# isoSP_UART_Test_Board_rev1.net
KiCad netlist of a schematic drawn in EAGLE
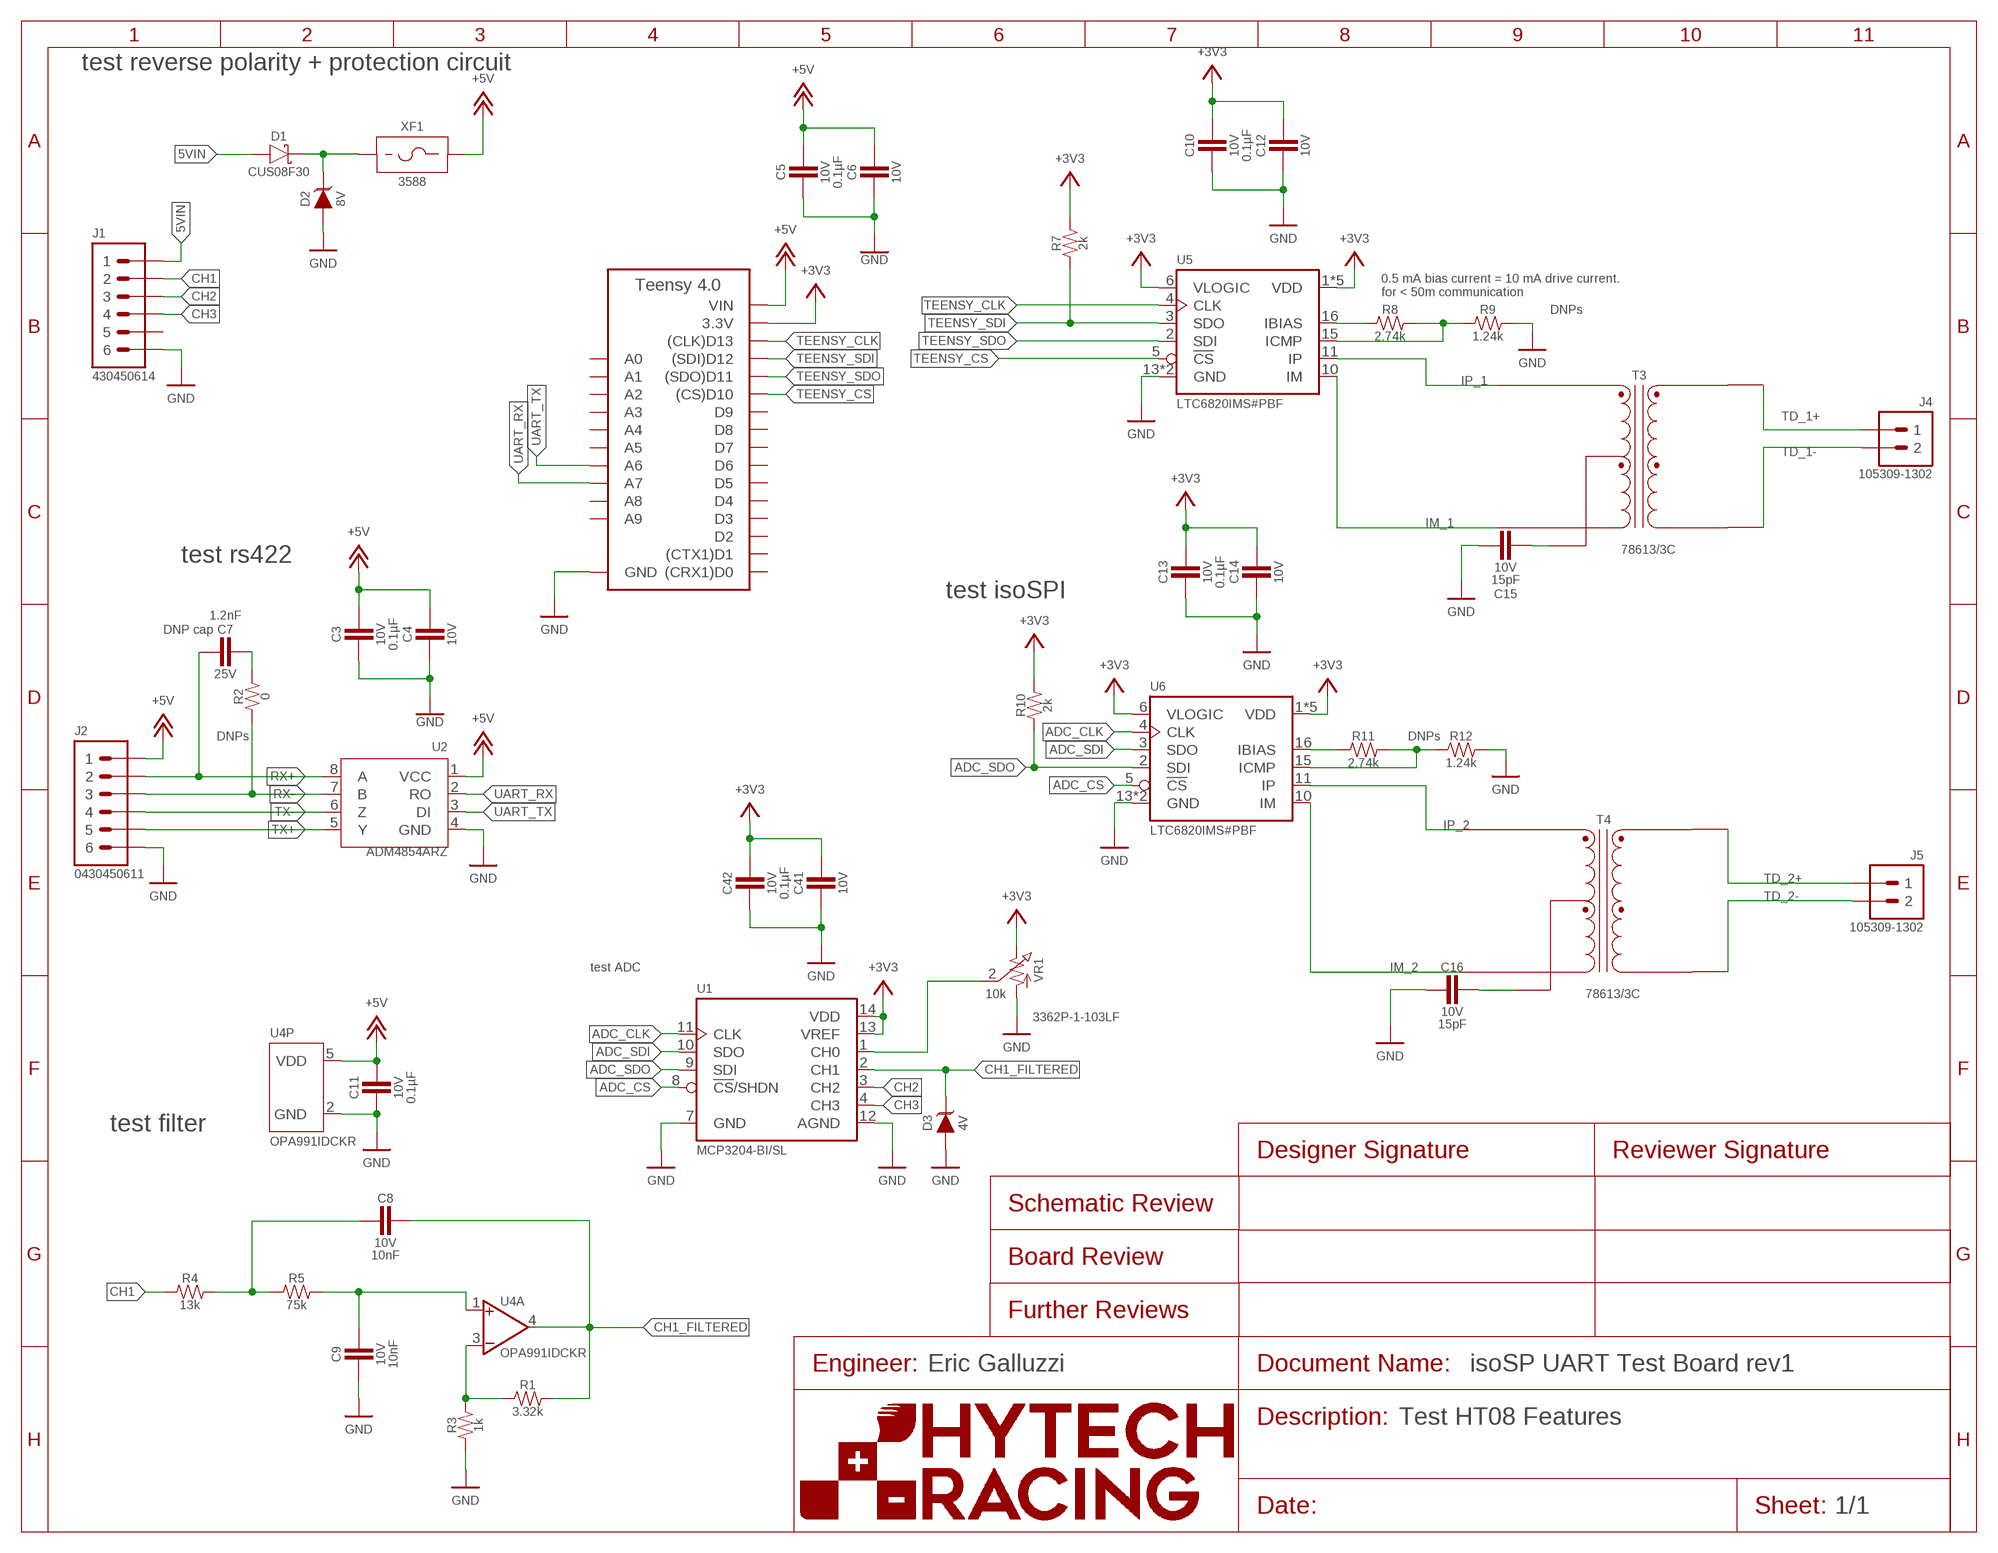
[diagram p0: schematic, sheet 1]

(export (version "E")
  (design (tool "Eeschema 10.0.6"))
  (components
    (comp (ref "A1")
      (value "TEENSY_4.0TH")
      (footprint "eagle-import:TEENSY_SHORT")
      (libsource (lib "eagle-import") (part "TEENSY_4.0TH"))
    )
    (comp (ref "C3")
      (value "CAPACITOR_0603_10V_0.1UF")
      (footprint "eagle-import:0603-CAP")
      (fields
        (field (name "CAPACITANCE") "0.1µF")
        (field (name "MANUFACTURER") "Vishay Vitramon")
        (field (name "MPN") "VJ0603Y104JXQPW1BC")
        (field (name "TOLERANCE") "5%")
        (field (name "VOLTAGE") "10V")
      )
      (libsource (lib "eagle-import") (part "CAPACITOR_?_060310V_0.1UF"))
    )
    (comp (ref "C4")
      (value "CAPACITOR_0603_10V_1UF")
      (footprint "eagle-import:0603-CAP")
      (fields
        (field (name "MANUFACTURER") "Yageo")
        (field (name "MPN") "CC0603KRX7R6BB105")
        (field (name "TOLERANCE") "10%")
        (field (name "VOLTAGE") "10V")
      )
      (libsource (lib "eagle-import") (part "CAPACITOR_?_060310V_1UF"))
    )
    (comp (ref "C5")
      (value "CAPACITOR_0603_10V_0.1UF")
      (footprint "eagle-import:0603-CAP")
      (fields
        (field (name "CAPACITANCE") "0.1µF")
        (field (name "MANUFACTURER") "Vishay Vitramon")
        (field (name "MPN") "VJ0603Y104JXQPW1BC")
        (field (name "TOLERANCE") "5%")
        (field (name "VOLTAGE") "10V")
      )
      (libsource (lib "eagle-import") (part "CAPACITOR_?_060310V_0.1UF"))
    )
    (comp (ref "C6")
      (value "CAPACITOR_0603_10V_1UF")
      (footprint "eagle-import:0603-CAP")
      (fields
        (field (name "MANUFACTURER") "Yageo")
        (field (name "MPN") "CC0603KRX7R6BB105")
        (field (name "TOLERANCE") "10%")
        (field (name "VOLTAGE") "10V")
      )
      (libsource (lib "eagle-import") (part "CAPACITOR_?_060310V_1UF"))
    )
    (comp (ref "C7")
      (value "CAPACITOR_0603_25V_1.2NF")
      (footprint "eagle-import:0603-CAP")
      (fields
        (field (name "CAPACITANCE") "1.2nF")
        (field (name "MANUFACTURER") "YAGEO")
        (field (name "MPN") "CC0603KRX7R8BB122")
        (field (name "TOLERANCE") "10%")
        (field (name "VOLTAGE") "25V")
      )
      (libsource (lib "eagle-import") (part "CAPACITOR_?_060325V_1.2NF"))
    )
    (comp (ref "C8")
      (value "CAPACITOR_0603_10V_10NF")
      (footprint "eagle-import:0603-CAP")
      (fields
        (field (name "CAPACITANCE") "10nF")
        (field (name "MANUFACTURER") "Yageo")
        (field (name "MPN") "CC0603KRX7R6BB103")
        (field (name "TOLERANCE") "10%")
        (field (name "VOLTAGE") "10V")
      )
      (libsource (lib "eagle-import") (part "CAPACITOR_?_060310V_10NF"))
    )
    (comp (ref "C9")
      (value "CAPACITOR_0603_10V_10NF")
      (footprint "eagle-import:0603-CAP")
      (fields
        (field (name "CAPACITANCE") "10nF")
        (field (name "MANUFACTURER") "Yageo")
        (field (name "MPN") "CC0603KRX7R6BB103")
        (field (name "TOLERANCE") "10%")
        (field (name "VOLTAGE") "10V")
      )
      (libsource (lib "eagle-import") (part "CAPACITOR_?_060310V_10NF"))
    )
    (comp (ref "C10")
      (value "CAPACITOR_0603_10V_0.1UF")
      (footprint "eagle-import:0603-CAP")
      (fields
        (field (name "CAPACITANCE") "0.1µF")
        (field (name "MANUFACTURER") "Vishay Vitramon")
        (field (name "MPN") "VJ0603Y104JXQPW1BC")
        (field (name "TOLERANCE") "5%")
        (field (name "VOLTAGE") "10V")
      )
      (libsource (lib "eagle-import") (part "CAPACITOR_?_060310V_0.1UF"))
    )
    (comp (ref "C11")
      (value "CAPACITOR_0603_10V_0.1UF")
      (footprint "eagle-import:0603-CAP")
      (fields
        (field (name "CAPACITANCE") "0.1µF")
        (field (name "MANUFACTURER") "Vishay Vitramon")
        (field (name "MPN") "VJ0603Y104JXQPW1BC")
        (field (name "TOLERANCE") "5%")
        (field (name "VOLTAGE") "10V")
      )
      (libsource (lib "eagle-import") (part "CAPACITOR_?_060310V_0.1UF"))
    )
    (comp (ref "C12")
      (value "CAPACITOR_0603_10V_1UF")
      (footprint "eagle-import:0603-CAP")
      (fields
        (field (name "MANUFACTURER") "Yageo")
        (field (name "MPN") "CC0603KRX7R6BB105")
        (field (name "TOLERANCE") "10%")
        (field (name "VOLTAGE") "10V")
      )
      (libsource (lib "eagle-import") (part "CAPACITOR_?_060310V_1UF"))
    )
    (comp (ref "C13")
      (value "CAPACITOR_0603_10V_0.1UF")
      (footprint "eagle-import:0603-CAP")
      (fields
        (field (name "CAPACITANCE") "0.1µF")
        (field (name "MANUFACTURER") "Vishay Vitramon")
        (field (name "MPN") "VJ0603Y104JXQPW1BC")
        (field (name "TOLERANCE") "5%")
        (field (name "VOLTAGE") "10V")
      )
      (libsource (lib "eagle-import") (part "CAPACITOR_?_060310V_0.1UF"))
    )
    (comp (ref "C14")
      (value "CAPACITOR_0603_10V_1UF")
      (footprint "eagle-import:0603-CAP")
      (fields
        (field (name "MANUFACTURER") "Yageo")
        (field (name "MPN") "CC0603KRX7R6BB105")
        (field (name "TOLERANCE") "10%")
        (field (name "VOLTAGE") "10V")
      )
      (libsource (lib "eagle-import") (part "CAPACITOR_?_060310V_1UF"))
    )
    (comp (ref "C15")
      (value "CAPACITOR_0603_10V_15PF")
      (footprint "eagle-import:0603-CAP")
      (fields
        (field (name "CAPACITANCE") "15pF")
        (field (name "MANUFACTURER") "Vishay Vitramon")
        (field (name "MPN") "VJ0603A150FXQPW1BC")
        (field (name "TOLERANCE") "1%")
        (field (name "VOLTAGE") "10V")
      )
      (libsource (lib "eagle-import") (part "CAPACITOR_?_060310V_15PF"))
    )
    (comp (ref "C16")
      (value "CAPACITOR_0603_10V_15PF")
      (footprint "eagle-import:0603-CAP")
      (fields
        (field (name "CAPACITANCE") "15pF")
        (field (name "MANUFACTURER") "Vishay Vitramon")
        (field (name "MPN") "VJ0603A150FXQPW1BC")
        (field (name "TOLERANCE") "1%")
        (field (name "VOLTAGE") "10V")
      )
      (libsource (lib "eagle-import") (part "CAPACITOR_?_060310V_15PF"))
    )
    (comp (ref "C41")
      (value "CAPACITOR_0603_10V_1UF")
      (footprint "eagle-import:0603-CAP")
      (fields
        (field (name "MANUFACTURER") "Yageo")
        (field (name "MPN") "CC0603KRX7R6BB105")
        (field (name "TOLERANCE") "10%")
        (field (name "VOLTAGE") "10V")
      )
      (libsource (lib "eagle-import") (part "CAPACITOR_?_060310V_1UF"))
    )
    (comp (ref "C42")
      (value "CAPACITOR_0603_10V_0.1UF")
      (footprint "eagle-import:0603-CAP")
      (fields
        (field (name "CAPACITANCE") "0.1µF")
        (field (name "MANUFACTURER") "Vishay Vitramon")
        (field (name "MPN") "VJ0603Y104JXQPW1BC")
        (field (name "TOLERANCE") "5%")
        (field (name "VOLTAGE") "10V")
      )
      (libsource (lib "eagle-import") (part "CAPACITOR_?_060310V_0.1UF"))
    )
    (comp (ref "D1")
      (value "SCHOTTKY_SOD323_30V")
      (footprint "eagle-import:SOD-323")
      (fields
        (field (name "MANUFACTURER") "Toshiba Semiconductor and Storage")
        (field (name "MPN") "CUS08F30")
        (field (name "VOLTAGE") "30V")
      )
      (libsource (lib "eagle-import") (part "SCHOTTKY_?_SOD32330V"))
    )
    (comp (ref "D2")
      (value "TVS__8V")
      (footprint "eagle-import:SOT-23")
      (fields
        (field (name "MANUFACTURER") "Vishay General Semiconductor - Diodes Division")
        (field (name "MPN") "GSOT08-E3-08")
        (field (name "VOLTAGE") "8V")
      )
      (libsource (lib "eagle-import") (part "TVS_?_8V"))
    )
    (comp (ref "D3")
      (value "TVS__4V")
      (footprint "eagle-import:SOT-23")
      (fields
        (field (name "MANUFACTURER") "Vishay General Semiconductor - Diodes Division")
        (field (name "MPN") "GSOT04-E3-08")
        (field (name "VOLTAGE") "4V")
      )
      (libsource (lib "eagle-import") (part "TVS_?_4V"))
    )
    (comp (ref "J1")
      (value "CONNECTOR-6_μF_T_V_BLACK")
      (footprint "eagle-import:MOLEX_MICROFIT_PTH_VERTICAL_06_DUAL")
      (fields (field (name "MANUFACTURER") "Molex") (field (name "MPN") "430450614"))
      (libsource (lib "eagle-import") (part "CONNECTOR-6_?_μF_T_VBLACK"))
    )
    (comp (ref "J2")
      (value "CONNECTOR-6_μF_S_RA_")
      (footprint "eagle-import:MOLEX_MICROFIT_SMD_RIGHTANGLE_06_DUAL")
      (fields (field (name "MPN") "0430450611") (field (name "MANUFACTURER") "Molex"))
      (libsource (lib "eagle-import") (part "CONNECTOR-6_?_μF_S_RA"))
    )
    (comp (ref "J4")
      (value "CONNECTOR-2_MOLEX_NANOFIT_PTH_VERTICAL_02_BLACK")
      (footprint "eagle-import:MOLEX_NANOFIT_PTH_02")
      (fields (field (name "MANUFACTURER") "Molex") (field (name "MPN") "105309-1302"))
      (libsource (lib "eagle-import") (part "CONNECTOR-2_?_MOLEX_NANOFIT_PTH_VERTICAL_02BLACK"))
    )
    (comp (ref "J5")
      (value "CONNECTOR-2_MOLEX_NANOFIT_PTH_VERTICAL_02_BLACK")
      (footprint "eagle-import:MOLEX_NANOFIT_PTH_02")
      (fields (field (name "MANUFACTURER") "Molex") (field (name "MPN") "105309-1302"))
      (libsource (lib "eagle-import") (part "CONNECTOR-2_?_MOLEX_NANOFIT_PTH_VERTICAL_02BLACK"))
    )
    (comp (ref "R1")
      (value "RESISTOR_0603_3.32K")
      (footprint "eagle-import:0603-RES")
      (fields
        (field (name "MANUFACTURER") "Yageo")
        (field (name "MPN") "RT0603BRD073K32L")
        (field (name "POWER") "0.1W")
        (field (name "RESISTANCE") "3.32k")
      )
      (libsource (lib "eagle-import") (part "RESISTOR_?_06033.32K"))
    )
    (comp (ref "R2")
      (value "RESISTOR_0603_0")
      (footprint "eagle-import:0603-RES")
      (fields
        (field (name "MANUFACTURER") "Yageo")
        (field (name "MPN") "RC0603FR-070RL")
        (field (name "POWER") "0.1W")
        (field (name "RESISTANCE") "0")
      )
      (libsource (lib "eagle-import") (part "RESISTOR_?_06030"))
    )
    (comp (ref "R3")
      (value "RESISTOR_0603_1K")
      (footprint "eagle-import:0603-RES")
      (fields
        (field (name "MANUFACTURER") "TE Connectivity Passive Product")
        (field (name "MPN") " CPF-A-0603B1K0E")
        (field (name "POWER") "0.0625W")
        (field (name "RESISTANCE") "1k")
      )
      (libsource (lib "eagle-import") (part "RESISTOR_?_06031K"))
    )
    (comp (ref "R4")
      (value "RESISTOR_0603_13K")
      (footprint "eagle-import:0603-RES")
      (fields
        (field (name "MANUFACTURER") "Panasonic Electronic Components")
        (field (name "MPN") "ERA-3ARW133V")
        (field (name "POWER") "0.1W")
        (field (name "RESISTANCE") "13k")
      )
      (libsource (lib "eagle-import") (part "RESISTOR_?_060313K"))
    )
    (comp (ref "R5")
      (value "RESISTOR_0603_75K")
      (footprint "eagle-import:0603-RES")
      (fields
        (field (name "MANUFACTURER") "Yageo")
        (field (name "MPN") "RT0603BRE0775KL")
        (field (name "POWER") "0.1W")
        (field (name "RESISTANCE") "75k")
      )
      (libsource (lib "eagle-import") (part "RESISTOR_?_060375K"))
    )
    (comp (ref "R7")
      (value "RESISTOR_0603_2K")
      (footprint "eagle-import:0603-RES")
      (fields
        (field (name "MANUFACTURER") "Panasonic Electronic Components")
        (field (name "MPN") "ERJ-UP3F2001V")
        (field (name "POWER") "0.25W")
        (field (name "RESISTANCE") "2k")
      )
      (libsource (lib "eagle-import") (part "RESISTOR_?_06032K"))
    )
    (comp (ref "R8")
      (value "RESISTOR_0603_2.74K")
      (footprint "eagle-import:0603-RES")
      (fields
        (field (name "MANUFACTURER") "Panasonic Electronic Components")
        (field (name "MPN") "ERJ-PB3B2741V")
        (field (name "POWER") "0.2W")
        (field (name "RESISTANCE") "2.74k")
      )
      (libsource (lib "eagle-import") (part "RESISTOR_?_06032.74K"))
    )
    (comp (ref "R9")
      (value "RESISTOR_0603_1.24K")
      (footprint "eagle-import:0603-RES")
      (fields
        (field (name "MANUFACTURER") "Yageo")
        (field (name "MPN") "RC0603FR-071K24L")
        (field (name "POWER") "0.1W")
        (field (name "RESISTANCE") "1.24k")
      )
      (libsource (lib "eagle-import") (part "RESISTOR_?_06031.24K"))
    )
    (comp (ref "R10")
      (value "RESISTOR_0603_2K")
      (footprint "eagle-import:0603-RES")
      (fields
        (field (name "MANUFACTURER") "Panasonic Electronic Components")
        (field (name "MPN") "ERJ-UP3F2001V")
        (field (name "POWER") "0.25W")
        (field (name "RESISTANCE") "2k")
      )
      (libsource (lib "eagle-import") (part "RESISTOR_?_06032K"))
    )
    (comp (ref "R11")
      (value "RESISTOR_0603_2.74K")
      (footprint "eagle-import:0603-RES")
      (fields
        (field (name "MANUFACTURER") "Panasonic Electronic Components")
        (field (name "MPN") "ERJ-PB3B2741V")
        (field (name "POWER") "0.2W")
        (field (name "RESISTANCE") "2.74k")
      )
      (libsource (lib "eagle-import") (part "RESISTOR_?_06032.74K"))
    )
    (comp (ref "R12")
      (value "RESISTOR_0603_1.24K")
      (footprint "eagle-import:0603-RES")
      (fields
        (field (name "MANUFACTURER") "Yageo")
        (field (name "MPN") "RC0603FR-071K24L")
        (field (name "POWER") "0.1W")
        (field (name "RESISTANCE") "1.24k")
      )
      (libsource (lib "eagle-import") (part "RESISTOR_?_06031.24K"))
    )
    (comp (ref "T3")
      (value "78613/3C")
      (footprint "eagle-import:78613_3C")
      (fields (field (name "MPN") "78613/3C") (field (name "MANUFACTURER") "Murata Power Solutions"))
      (libsource (lib "eagle-import") (part "78613/3C"))
    )
    (comp (ref "T4")
      (value "78613/3C")
      (footprint "eagle-import:78613_3C")
      (fields (field (name "MPN") "78613/3C") (field (name "MANUFACTURER") "Murata Power Solutions"))
      (libsource (lib "eagle-import") (part "78613/3C"))
    )
    (comp (ref "U1")
      (value "MCP3204")
      (footprint "eagle-import:SOIC-14")
      (fields (field (name "MPN") "MCP3204-BI/SL") (field (name "MANUFACTURER") "Microchip Technology"))
      (libsource (lib "eagle-import") (part "MCP3204"))
    )
    (comp (ref "U2")
      (value "ADM4854ARZ")
      (footprint "eagle-import:SOIC-08(NARROW,0.15_)")
      (fields (field (name "MPN") "ADM4854ARZ") (field (name "MANUFACTURER") "Analog Devices Inc."))
      (libsource (lib "eagle-import") (part "ADM4854ARZ"))
    )
    (comp (ref "U4")
      (value "OPAMP_1_CHANNEL_OPA991")
      (footprint "eagle-import:SC-70-5")
      (fields (field (name "MANUFACTURER") "Texas Instruments") (field (name "MPN") "OPA991IDCKR"))
      (libsource (lib "eagle-import") (part "OPAMP_1_CHANNEL_OPA991"))
    )
    (comp (ref "U5")
      (value "LTC6820")
      (footprint "eagle-import:MSOP-16")
      (fields (field (name "MPN") "LTC6820IMS#PBF") (field (name "MANUFACTURER") "Analog Devices"))
      (libsource (lib "eagle-import") (part "LTC6820"))
    )
    (comp (ref "U6")
      (value "LTC6820")
      (footprint "eagle-import:MSOP-16")
      (fields (field (name "MPN") "LTC6820IMS#PBF") (field (name "MANUFACTURER") "Analog Devices"))
      (libsource (lib "eagle-import") (part "LTC6820"))
    )
    (comp (ref "VR1")
      (value "RESISTOR_TRIMPOT_10K_3362P")
      (footprint "eagle-import:3362P")
      (fields
        (field (name "MANUFACTURER") "Bourns Inc.")
        (field (name "MPN") "3362P-1-103LF")
        (field (name "POWER") "0.5W")
        (field (name "RESISTANCE") "10k")
        (field (name "TOLERANCE") "10%")
      )
      (libsource (lib "eagle-import") (part "RESISTOR_TRIMPOT__?3362P10K"))
    )
    (comp (ref "XF1")
      (value "FUSE_HOLDER_MINIBLADESMD")
      (footprint "eagle-import:3588")
      (fields (field (name "MANUFACTURER") "Keystone Electronics") (field (name "MPN") "3588"))
      (libsource (lib "eagle-import") (part "FUSE_HOLDER_SMDMINIBLADE"))
    )
  )
  (nets
    (net (code "1") (name "+3V3") (class "Default")
      (node (ref "A1") (pin "3.3V") (pinfunction "3.3V_3.3V") (pintype "power_in"))
      (node (ref "C10") (pin "1") (pinfunction "1_1") (pintype "passive"))
      (node (ref "C12") (pin "1") (pinfunction "1_1") (pintype "passive"))
      (node (ref "C13") (pin "1") (pinfunction "1_1") (pintype "passive"))
      (node (ref "C14") (pin "1") (pinfunction "1_1") (pintype "passive"))
      (node (ref "C41") (pin "1") (pinfunction "1_1") (pintype "passive"))
      (node (ref "C42") (pin "1") (pinfunction "1_1") (pintype "passive"))
      (node (ref "R10") (pin "2") (pinfunction "2_2") (pintype "passive"))
      (node (ref "R7") (pin "2") (pinfunction "2_2") (pintype "passive"))
      (node (ref "U1") (pin "13") (pinfunction "VREF_13") (pintype "power_in"))
      (node (ref "U1") (pin "14") (pinfunction "VDD_14") (pintype "power_in"))
      (node (ref "U5") (pin "1") (pinfunction "VDD_1") (pintype "power_in"))
      (node (ref "U5") (pin "12") (pinfunction "VDD_12") (pintype "power_in"))
      (node (ref "U5") (pin "6") (pinfunction "VLOGIC_6") (pintype "bidirectional"))
      (node (ref "U5") (pin "7") (pinfunction "VDD_7") (pintype "power_in"))
      (node (ref "U5") (pin "8") (pinfunction "VDD_8") (pintype "power_in"))
      (node (ref "U5") (pin "9") (pinfunction "VDD_9") (pintype "power_in"))
      (node (ref "U6") (pin "1") (pinfunction "VDD_1") (pintype "power_in"))
      (node (ref "U6") (pin "12") (pinfunction "VDD_12") (pintype "power_in"))
      (node (ref "U6") (pin "6") (pinfunction "VLOGIC_6") (pintype "bidirectional"))
      (node (ref "U6") (pin "7") (pinfunction "VDD_7") (pintype "power_in"))
      (node (ref "U6") (pin "8") (pinfunction "VDD_8") (pintype "power_in"))
      (node (ref "U6") (pin "9") (pinfunction "VDD_9") (pintype "power_in"))
      (node (ref "VR1") (pin "3") (pinfunction "2_3") (pintype "passive"))
    )
    (net (code "2") (name "+5V") (class "Default")
      (node (ref "A1") (pin "VIN") (pinfunction "VIN_VIN") (pintype "power_in"))
      (node (ref "C11") (pin "1") (pinfunction "1_1") (pintype "passive"))
      (node (ref "C3") (pin "1") (pinfunction "1_1") (pintype "passive"))
      (node (ref "C4") (pin "1") (pinfunction "1_1") (pintype "passive"))
      (node (ref "C5") (pin "1") (pinfunction "1_1") (pintype "passive"))
      (node (ref "C6") (pin "1") (pinfunction "1_1") (pintype "passive"))
      (node (ref "J2") (pin "1") (pinfunction "1_1") (pintype "passive"))
      (node (ref "U2") (pin "1") (pinfunction "VCC_1") (pintype "passive"))
      (node (ref "U4") (pin "5") (pinfunction "VDD_5") (pintype "power_in"))
      (node (ref "XF1") (pin "3") (pinfunction "2_3") (pintype "passive"))
      (node (ref "XF1") (pin "4") (pinfunction "2_4") (pintype "passive"))
    )
    (net (code "3") (name "/IM_1") (class "Default")
      (node (ref "T3") (pin "2") (pinfunction "PRI_2_2") (pintype "passive"))
      (node (ref "U5") (pin "10") (pinfunction "IM_10") (pintype "bidirectional"))
    )
    (net (code "4") (name "/IM_2") (class "Default")
      (node (ref "T4") (pin "2") (pinfunction "PRI_2_2") (pintype "passive"))
      (node (ref "U6") (pin "10") (pinfunction "IM_10") (pintype "bidirectional"))
    )
    (net (code "5") (name "/IP_1") (class "Default")
      (node (ref "T3") (pin "1") (pinfunction "PRI_1_1") (pintype "passive"))
      (node (ref "U5") (pin "11") (pinfunction "IP_11") (pintype "bidirectional"))
    )
    (net (code "6") (name "/IP_2") (class "Default")
      (node (ref "T4") (pin "1") (pinfunction "PRI_1_1") (pintype "passive"))
      (node (ref "U6") (pin "11") (pinfunction "IP_11") (pintype "bidirectional"))
    )
    (net (code "7") (name "/TD_1+") (class "Default")
      (node (ref "J4") (pin "1") (pinfunction "1_1") (pintype "passive"))
      (node (ref "T3") (pin "6") (pinfunction "SEC_2_6") (pintype "passive"))
    )
    (net (code "8") (name "/TD_1-") (class "Default")
      (node (ref "J4") (pin "2") (pinfunction "2_2") (pintype "passive"))
      (node (ref "T3") (pin "4") (pinfunction "SEC_1_4") (pintype "passive"))
    )
    (net (code "9") (name "/TD_2+") (class "Default")
      (node (ref "J5") (pin "1") (pinfunction "1_1") (pintype "passive"))
      (node (ref "T4") (pin "6") (pinfunction "SEC_2_6") (pintype "passive"))
    )
    (net (code "10") (name "/TD_2-") (class "Default")
      (node (ref "J5") (pin "2") (pinfunction "2_2") (pintype "passive"))
      (node (ref "T4") (pin "4") (pinfunction "SEC_1_4") (pintype "passive"))
    )
    (net (code "11") (name "5VIN") (class "Default")
      (node (ref "D1") (pin "A") (pinfunction "A_A") (pintype "passive"))
      (node (ref "J1") (pin "1") (pinfunction "1_1") (pintype "passive"))
    )
    (net (code "12") (name "ADC_CLK") (class "Default")
      (node (ref "U1") (pin "11") (pinfunction "CLK_11") (pintype "input"))
      (node (ref "U6") (pin "4") (pinfunction "CLK_4") (pintype "input"))
    )
    (net (code "13") (name "ADC_CS") (class "Default")
      (node (ref "U1") (pin "8") (pinfunction "~{CS}/SHDN_8") (pintype "input"))
      (node (ref "U6") (pin "5") (pinfunction "~{CS}_5") (pintype "input"))
    )
    (net (code "14") (name "ADC_SDI") (class "Default")
      (node (ref "U1") (pin "10") (pinfunction "SDO_10") (pintype "output"))
      (node (ref "U6") (pin "3") (pinfunction "SDO_3") (pintype "open_collector"))
    )
    (net (code "15") (name "ADC_SDO") (class "Default")
      (node (ref "R10") (pin "1") (pinfunction "1_1") (pintype "passive"))
      (node (ref "U1") (pin "9") (pinfunction "SDI_9") (pintype "input"))
      (node (ref "U6") (pin "2") (pinfunction "SDI_2") (pintype "open_collector"))
    )
    (net (code "16") (name "CH1") (class "Default")
      (node (ref "J1") (pin "2") (pinfunction "2_2") (pintype "passive"))
      (node (ref "R4") (pin "1") (pinfunction "1_1") (pintype "passive"))
    )
    (net (code "17") (name "CH1_FILTERED") (class "Default")
      (node (ref "C8") (pin "1") (pinfunction "1_1") (pintype "passive"))
      (node (ref "D3") (pin "3") (pinfunction "C_3") (pintype "passive"))
      (node (ref "R1") (pin "2") (pinfunction "2_2") (pintype "passive"))
      (node (ref "U1") (pin "2") (pinfunction "CH1_2") (pintype "input"))
      (node (ref "U4") (pin "4") (pinfunction "VOUT_4") (pintype "output"))
    )
    (net (code "18") (name "CH2") (class "Default")
      (node (ref "J1") (pin "3") (pinfunction "3_3") (pintype "passive"))
      (node (ref "U1") (pin "3") (pinfunction "CH2_3") (pintype "input"))
    )
    (net (code "19") (name "CH3") (class "Default")
      (node (ref "J1") (pin "4") (pinfunction "4_4") (pintype "passive"))
      (node (ref "U1") (pin "4") (pinfunction "CH3_4") (pintype "input"))
    )
    (net (code "20") (name "GND") (class "Default")
      (node (ref "A1") (pin "AGND/GND") (pinfunction "GND_AGND/GND") (pintype "power_in"))
      (node (ref "A1") (pin "GND") (pinfunction "GND_GND") (pintype "power_in"))
      (node (ref "C10") (pin "2") (pinfunction "2_2") (pintype "passive"))
      (node (ref "C11") (pin "2") (pinfunction "2_2") (pintype "passive"))
      (node (ref "C12") (pin "2") (pinfunction "2_2") (pintype "passive"))
      (node (ref "C13") (pin "2") (pinfunction "2_2") (pintype "passive"))
      (node (ref "C14") (pin "2") (pinfunction "2_2") (pintype "passive"))
      (node (ref "C15") (pin "2") (pinfunction "2_2") (pintype "passive"))
      (node (ref "C16") (pin "2") (pinfunction "2_2") (pintype "passive"))
      (node (ref "C3") (pin "2") (pinfunction "2_2") (pintype "passive"))
      (node (ref "C4") (pin "2") (pinfunction "2_2") (pintype "passive"))
      (node (ref "C41") (pin "2") (pinfunction "2_2") (pintype "passive"))
      (node (ref "C42") (pin "2") (pinfunction "2_2") (pintype "passive"))
      (node (ref "C5") (pin "2") (pinfunction "2_2") (pintype "passive"))
      (node (ref "C6") (pin "2") (pinfunction "2_2") (pintype "passive"))
      (node (ref "C9") (pin "2") (pinfunction "2_2") (pintype "passive"))
      (node (ref "D2") (pin "1") (pinfunction "A_1") (pintype "passive"))
      (node (ref "D3") (pin "1") (pinfunction "A_1") (pintype "passive"))
      (node (ref "J1") (pin "6") (pinfunction "6_6") (pintype "passive"))
      (node (ref "J2") (pin "6") (pinfunction "6_6") (pintype "passive"))
      (node (ref "R12") (pin "2") (pinfunction "2_2") (pintype "passive"))
      (node (ref "R3") (pin "1") (pinfunction "1_1") (pintype "passive"))
      (node (ref "R9") (pin "2") (pinfunction "2_2") (pintype "passive"))
      (node (ref "U1") (pin "12") (pinfunction "AGND_12") (pintype "power_in"))
      (node (ref "U1") (pin "7") (pinfunction "GND_7") (pintype "power_in"))
      (node (ref "U2") (pin "4") (pinfunction "GND_4") (pintype "passive"))
      (node (ref "U4") (pin "2") (pinfunction "GND_2") (pintype "power_in"))
      (node (ref "U5") (pin "13") (pinfunction "GND_13") (pintype "power_in"))
      (node (ref "U5") (pin "14") (pinfunction "GND_14") (pintype "power_in"))
      (node (ref "U6") (pin "13") (pinfunction "GND_13") (pintype "power_in"))
      (node (ref "U6") (pin "14") (pinfunction "GND_14") (pintype "power_in"))
      (node (ref "VR1") (pin "1") (pinfunction "1_1") (pintype "passive"))
    )
    (net (code "21") (name "Net-(C7-Pad1)") (class "Default")
      (node (ref "C7") (pin "1") (pinfunction "1_1") (pintype "passive"))
      (node (ref "R2") (pin "2") (pinfunction "2_2") (pintype "passive"))
    )
    (net (code "22") (name "Net-(C8-Pad2)") (class "Default")
      (node (ref "C8") (pin "2") (pinfunction "2_2") (pintype "passive"))
      (node (ref "R4") (pin "2") (pinfunction "2_2") (pintype "passive"))
      (node (ref "R5") (pin "1") (pinfunction "1_1") (pintype "passive"))
    )
    (net (code "23") (name "Net-(D2-C)") (class "Default")
      (node (ref "D1") (pin "C") (pinfunction "C_C") (pintype "passive"))
      (node (ref "D2") (pin "3") (pinfunction "C_3") (pintype "passive"))
      (node (ref "XF1") (pin "1") (pinfunction "1_1") (pintype "passive"))
      (node (ref "XF1") (pin "2") (pinfunction "1_2") (pintype "passive"))
    )
    (net (code "24") (name "Net-(T3-PRI_CENTER_TAP)") (class "Default")
      (node (ref "C15") (pin "1") (pinfunction "1_1") (pintype "passive"))
      (node (ref "T3") (pin "3") (pinfunction "PRI_CENTER_TAP_3") (pintype "passive"))
    )
    (net (code "25") (name "Net-(T4-PRI_CENTER_TAP)") (class "Default")
      (node (ref "C16") (pin "1") (pinfunction "1_1") (pintype "passive"))
      (node (ref "T4") (pin "3") (pinfunction "PRI_CENTER_TAP_3") (pintype "passive"))
    )
    (net (code "26") (name "Net-(U1-CH0)") (class "Default")
      (node (ref "U1") (pin "1") (pinfunction "CH0_1") (pintype "input"))
      (node (ref "VR1") (pin "2") (pinfunction "3_2") (pintype "passive"))
    )
    (net (code "27") (name "Net-(U4A-VIN+)") (class "Default")
      (node (ref "C9") (pin "1") (pinfunction "1_1") (pintype "passive"))
      (node (ref "R5") (pin "2") (pinfunction "2_2") (pintype "passive"))
      (node (ref "U4") (pin "1") (pinfunction "VIN+_1") (pintype "input"))
    )
    (net (code "28") (name "Net-(U4A-VIN-)") (class "Default")
      (node (ref "R1") (pin "1") (pinfunction "1_1") (pintype "passive"))
      (node (ref "R3") (pin "2") (pinfunction "2_2") (pintype "passive"))
      (node (ref "U4") (pin "3") (pinfunction "VIN-_3") (pintype "input"))
    )
    (net (code "29") (name "Net-(U5-IBIAS)") (class "Default")
      (node (ref "R8") (pin "1") (pinfunction "1_1") (pintype "passive"))
      (node (ref "U5") (pin "16") (pinfunction "IBIAS_16") (pintype "bidirectional"))
    )
    (net (code "30") (name "Net-(U5-ICMP)") (class "Default")
      (node (ref "R8") (pin "2") (pinfunction "2_2") (pintype "passive"))
      (node (ref "R9") (pin "1") (pinfunction "1_1") (pintype "passive"))
      (node (ref "U5") (pin "15") (pinfunction "ICMP_15") (pintype "bidirectional"))
    )
    (net (code "31") (name "Net-(U6-IBIAS)") (class "Default")
      (node (ref "R11") (pin "1") (pinfunction "1_1") (pintype "passive"))
      (node (ref "U6") (pin "16") (pinfunction "IBIAS_16") (pintype "bidirectional"))
    )
    (net (code "32") (name "Net-(U6-ICMP)") (class "Default")
      (node (ref "R11") (pin "2") (pinfunction "2_2") (pintype "passive"))
      (node (ref "R12") (pin "1") (pinfunction "1_1") (pintype "passive"))
      (node (ref "U6") (pin "15") (pinfunction "ICMP_15") (pintype "bidirectional"))
    )
    (net (code "33") (name "RX+") (class "Default")
      (node (ref "C7") (pin "2") (pinfunction "2_2") (pintype "passive"))
      (node (ref "J2") (pin "2") (pinfunction "2_2") (pintype "passive"))
      (node (ref "U2") (pin "8") (pinfunction "A_8") (pintype "passive"))
    )
    (net (code "34") (name "RX-") (class "Default")
      (node (ref "J2") (pin "3") (pinfunction "3_3") (pintype "passive"))
      (node (ref "R2") (pin "1") (pinfunction "1_1") (pintype "passive"))
      (node (ref "U2") (pin "7") (pinfunction "B_7") (pintype "passive"))
    )
    (net (code "35") (name "TEENSY_CLK") (class "Default")
      (node (ref "A1") (pin "D13") (pinfunction "(CLK)D13_D13") (pintype "bidirectional"))
      (node (ref "U5") (pin "4") (pinfunction "CLK_4") (pintype "input"))
    )
    (net (code "36") (name "TEENSY_CS") (class "Default")
      (node (ref "A1") (pin "D10") (pinfunction "(CS)D10_D10") (pintype "bidirectional"))
      (node (ref "U5") (pin "5") (pinfunction "~{CS}_5") (pintype "input"))
    )
    (net (code "37") (name "TEENSY_SDI") (class "Default")
      (node (ref "A1") (pin "D12") (pinfunction "(SDI)D12_D12") (pintype "bidirectional"))
      (node (ref "R7") (pin "1") (pinfunction "1_1") (pintype "passive"))
      (node (ref "U5") (pin "3") (pinfunction "SDO_3") (pintype "open_collector"))
    )
    (net (code "38") (name "TEENSY_SDO") (class "Default")
      (node (ref "A1") (pin "D11") (pinfunction "(SDO)D11_D11") (pintype "bidirectional"))
      (node (ref "U5") (pin "2") (pinfunction "SDI_2") (pintype "open_collector"))
    )
    (net (code "39") (name "TX+") (class "Default")
      (node (ref "J2") (pin "5") (pinfunction "5_5") (pintype "passive"))
      (node (ref "U2") (pin "5") (pinfunction "Y_5") (pintype "passive"))
    )
    (net (code "40") (name "TX-") (class "Default")
      (node (ref "J2") (pin "4") (pinfunction "4_4") (pintype "passive"))
      (node (ref "U2") (pin "6") (pinfunction "Z_6") (pintype "passive"))
    )
    (net (code "41") (name "UART_RX") (class "Default")
      (node (ref "A1") (pin "D21") (pinfunction "A7_D21") (pintype "bidirectional"))
      (node (ref "U2") (pin "2") (pinfunction "RO_2") (pintype "passive"))
    )
    (net (code "42") (name "UART_TX") (class "Default")
      (node (ref "A1") (pin "D20") (pinfunction "A6_D20") (pintype "bidirectional"))
      (node (ref "U2") (pin "3") (pinfunction "DI_3") (pintype "passive"))
    )
    (net (code "43") (name "unconnected-(A1-(CRX1)D0-PadD0)") (class "Default")
      (node (ref "A1") (pin "D0") (pinfunction "(CRX1)D0_D0") (pintype "bidirectional"))
    )
    (net (code "44") (name "unconnected-(A1-(CTX1)D1-PadD1)") (class "Default")
      (node (ref "A1") (pin "D1") (pinfunction "(CTX1)D1_D1") (pintype "bidirectional"))
    )
    (net (code "45") (name "unconnected-(A1-A0-PadD14)") (class "Default")
      (node (ref "A1") (pin "D14") (pinfunction "A0_D14") (pintype "bidirectional"))
    )
    (net (code "46") (name "unconnected-(A1-A1-PadD15)") (class "Default")
      (node (ref "A1") (pin "D15") (pinfunction "A1_D15") (pintype "bidirectional"))
    )
    (net (code "47") (name "unconnected-(A1-A2-PadD16)") (class "Default")
      (node (ref "A1") (pin "D16") (pinfunction "A2_D16") (pintype "bidirectional"))
    )
    (net (code "48") (name "unconnected-(A1-A3-PadD17)") (class "Default")
      (node (ref "A1") (pin "D17") (pinfunction "A3_D17") (pintype "bidirectional"))
    )
    (net (code "49") (name "unconnected-(A1-A4-PadD18)") (class "Default")
      (node (ref "A1") (pin "D18") (pinfunction "A4_D18") (pintype "bidirectional"))
    )
    (net (code "50") (name "unconnected-(A1-A5-PadD19)") (class "Default")
      (node (ref "A1") (pin "D19") (pinfunction "A5_D19") (pintype "bidirectional"))
    )
    (net (code "51") (name "unconnected-(A1-A8-PadD22)") (class "Default")
      (node (ref "A1") (pin "D22") (pinfunction "A8_D22") (pintype "bidirectional"))
    )
    (net (code "52") (name "unconnected-(A1-A9-PadD23)") (class "Default")
      (node (ref "A1") (pin "D23") (pinfunction "A9_D23") (pintype "bidirectional"))
    )
    (net (code "53") (name "unconnected-(A1-PadD2)") (class "Default")
      (node (ref "A1") (pin "D2") (pinfunction "D2_D2") (pintype "bidirectional"))
    )
    (net (code "54") (name "unconnected-(A1-PadD3)") (class "Default")
      (node (ref "A1") (pin "D3") (pinfunction "D3_D3") (pintype "bidirectional"))
    )
    (net (code "55") (name "unconnected-(A1-PadD4)") (class "Default")
      (node (ref "A1") (pin "D4") (pinfunction "D4_D4") (pintype "bidirectional"))
    )
    (net (code "56") (name "unconnected-(A1-PadD5)") (class "Default")
      (node (ref "A1") (pin "D5") (pinfunction "D5_D5") (pintype "bidirectional"))
    )
    (net (code "57") (name "unconnected-(A1-PadD6)") (class "Default")
      (node (ref "A1") (pin "D6") (pinfunction "D6_D6") (pintype "bidirectional"))
    )
    (net (code "58") (name "unconnected-(A1-PadD7)") (class "Default")
      (node (ref "A1") (pin "D7") (pinfunction "D7_D7") (pintype "bidirectional"))
    )
    (net (code "59") (name "unconnected-(A1-PadD8)") (class "Default")
      (node (ref "A1") (pin "D8") (pinfunction "D8_D8") (pintype "bidirectional"))
    )
    (net (code "60") (name "unconnected-(A1-PadD9)") (class "Default")
      (node (ref "A1") (pin "D9") (pinfunction "D9_D9") (pintype "bidirectional"))
    )
    (net (code "61") (name "unconnected-(J1-Pad5)") (class "Default")
      (node (ref "J1") (pin "5") (pinfunction "5_5") (pintype "passive"))
    )
  )
)
